# JLPCB_DATA_LOGGER_schematic.net
KiCad netlist of a schematic drawn in EasyEDA
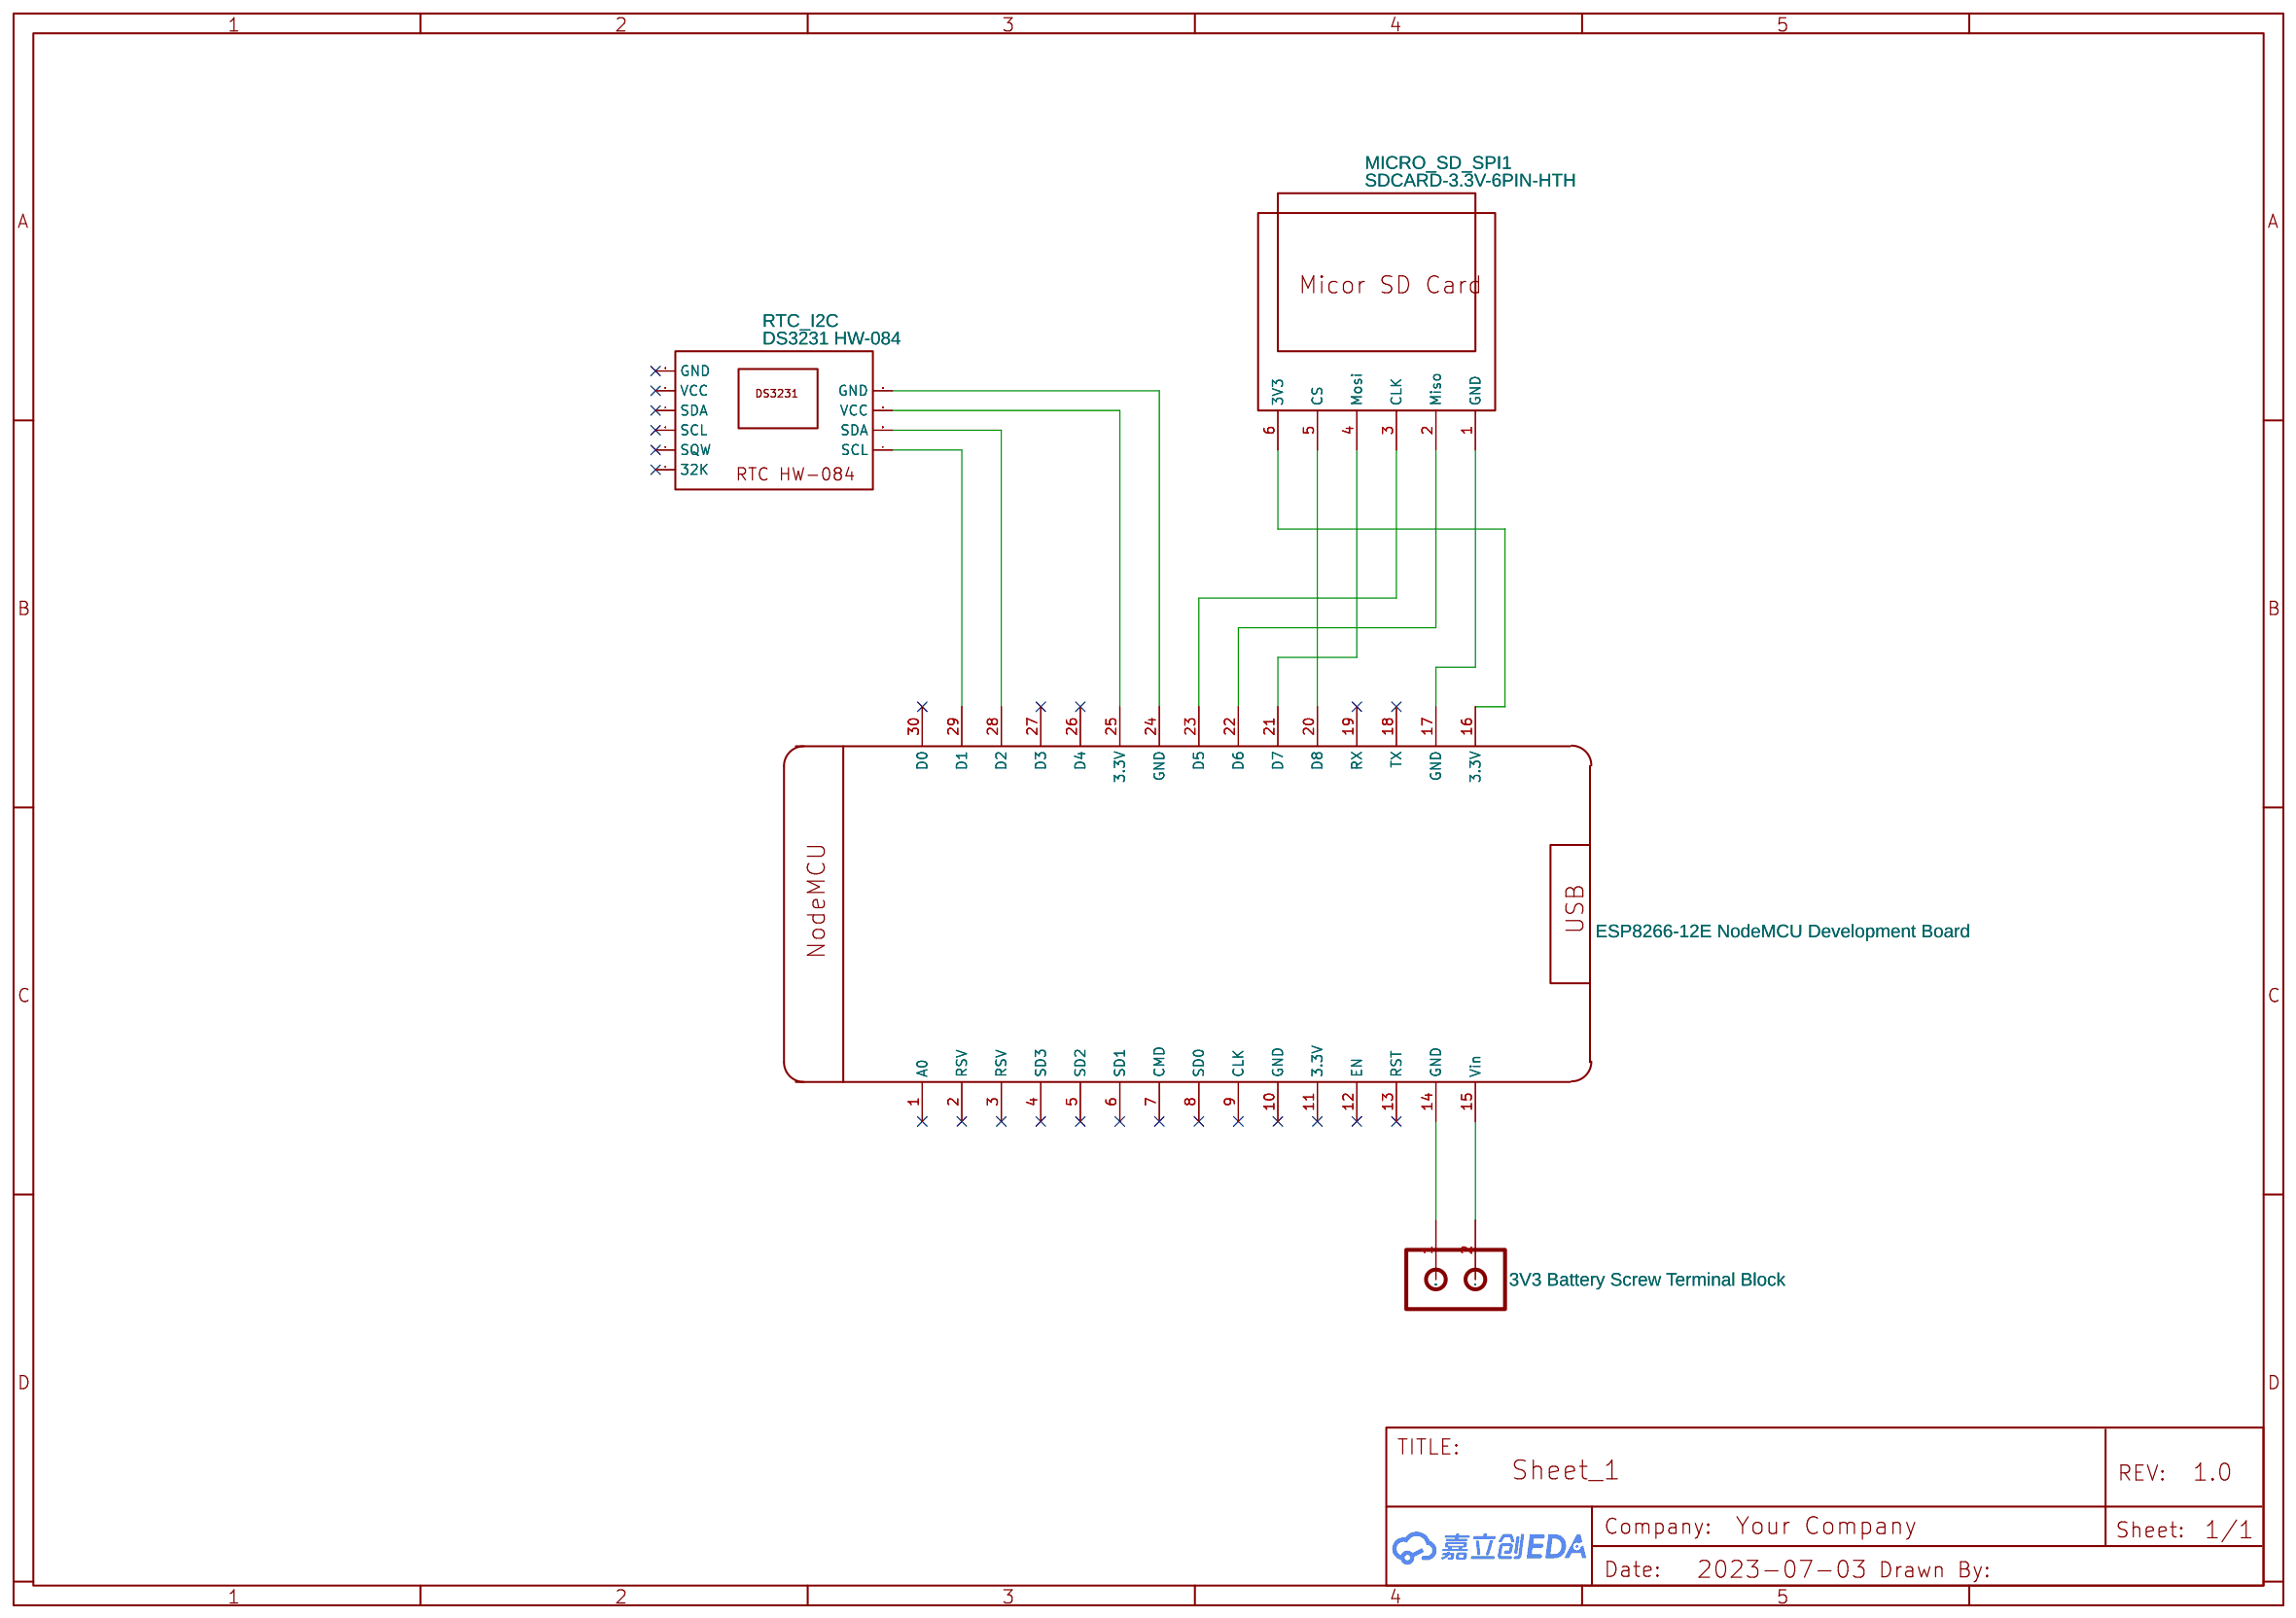
[diagram p0: schematic sheet]

(export (version "E")
  (design (tool "Eeschema 10.0.6"))
  (components
    (comp (ref "MICRO_SD_SPI1")
      (value "SDCARD-3.3V-6PIN-HTH")
      (fields (field (name "BOM_Manufacturer Part") "Aliexpress"))
      (libsource (lib "") (part "SDCARD-3.3V-6PIN-HTH"))
    )
    (comp (ref "NO1")
      (value "3V3 Battery Screw Terminal Block")
      (fields (field (name "BOM_Supplier Part") "HM3173"))
      (libsource (lib "") (part "Screw_Terminal_Block_2_Pin"))
    )
    (comp (ref "RTC_I2C") (value "DS3231 HW-084") (libsource (lib "") (part "DS3231 HW-084")))
    (comp (ref "U1")
      (value "ESP8266-12E NodeMCU Development Board")
      (libsource (lib "") (part "NODEMCU COPY"))
    )
  )
  (nets
    (net (code "1") (name "Net-(MICRO_SD_SPI1-3V3)") (class "Default")
      (node (ref "MICRO_SD_SPI1") (pin "6") (pinfunction "3V3_6") (pintype "unspecified"))
      (node (ref "U1") (pin "16") (pinfunction "3.3V_16") (pintype "unspecified"))
    )
    (net (code "2") (name "Net-(MICRO_SD_SPI1-CLK)") (class "Default")
      (node (ref "MICRO_SD_SPI1") (pin "3") (pinfunction "CLK_3") (pintype "unspecified"))
      (node (ref "U1") (pin "23") (pinfunction "D5_23") (pintype "unspecified"))
    )
    (net (code "3") (name "Net-(MICRO_SD_SPI1-CS)") (class "Default")
      (node (ref "MICRO_SD_SPI1") (pin "5") (pinfunction "CS_5") (pintype "unspecified"))
      (node (ref "U1") (pin "20") (pinfunction "D8_20") (pintype "unspecified"))
    )
    (net (code "4") (name "Net-(MICRO_SD_SPI1-GND)") (class "Default")
      (node (ref "MICRO_SD_SPI1") (pin "1") (pinfunction "GND_1") (pintype "unspecified"))
      (node (ref "U1") (pin "17") (pinfunction "GND_17") (pintype "unspecified"))
    )
    (net (code "5") (name "Net-(MICRO_SD_SPI1-Miso)") (class "Default")
      (node (ref "MICRO_SD_SPI1") (pin "2") (pinfunction "Miso_2") (pintype "unspecified"))
      (node (ref "U1") (pin "22") (pinfunction "D6_22") (pintype "unspecified"))
    )
    (net (code "6") (name "Net-(MICRO_SD_SPI1-Mosi)") (class "Default")
      (node (ref "MICRO_SD_SPI1") (pin "4") (pinfunction "Mosi_4") (pintype "unspecified"))
      (node (ref "U1") (pin "21") (pinfunction "D7_21") (pintype "unspecified"))
    )
    (net (code "7") (name "Net-(NO1-3V3)") (class "Default")
      (node (ref "NO1") (pin "2") (pinfunction "3V3_2") (pintype "passive"))
      (node (ref "U1") (pin "15") (pinfunction "Vin_15") (pintype "unspecified"))
    )
    (net (code "8") (name "Net-(NO1-GND)") (class "Default")
      (node (ref "NO1") (pin "1") (pinfunction "GND_1") (pintype "passive"))
      (node (ref "U1") (pin "14") (pinfunction "GND_14") (pintype "unspecified"))
    )
    (net (code "9") (name "Net-(RTC_I2C-GND-Pad10)") (class "Default")
      (node (ref "RTC_I2C") (pin "10") (pinfunction "GND_10") (pintype "unspecified"))
      (node (ref "U1") (pin "24") (pinfunction "GND_24") (pintype "unspecified"))
    )
    (net (code "10") (name "Net-(RTC_I2C-VCC-Pad9)") (class "Default")
      (node (ref "RTC_I2C") (pin "9") (pinfunction "VCC_9") (pintype "bidirectional"))
      (node (ref "U1") (pin "25") (pinfunction "3.3V_25") (pintype "unspecified"))
    )
    (net (code "11") (name "Net-(U1-D1)") (class "Default")
      (node (ref "RTC_I2C") (pin "7") (pinfunction "SCL_7") (pintype "passive"))
      (node (ref "U1") (pin "29") (pinfunction "D1_29") (pintype "unspecified"))
    )
    (net (code "12") (name "Net-(U1-D2)") (class "Default")
      (node (ref "RTC_I2C") (pin "8") (pinfunction "SDA_8") (pintype "passive"))
      (node (ref "U1") (pin "28") (pinfunction "D2_28") (pintype "unspecified"))
    )
    (net (code "13") (name "unconnected-(RTC_I2C-32K-Pad1)") (class "Default")
      (node (ref "RTC_I2C") (pin "1") (pinfunction "32K_1") (pintype "passive+no_connect"))
    )
    (net (code "14") (name "unconnected-(RTC_I2C-GND-Pad6)") (class "Default")
      (node (ref "RTC_I2C") (pin "6") (pinfunction "GND_6") (pintype "input+no_connect"))
    )
    (net (code "15") (name "unconnected-(RTC_I2C-SCL-Pad3)") (class "Default")
      (node (ref "RTC_I2C") (pin "3") (pinfunction "SCL_3") (pintype "bidirectional+no_connect"))
    )
    (net (code "16") (name "unconnected-(RTC_I2C-SDA-Pad4)") (class "Default")
      (node (ref "RTC_I2C") (pin "4") (pinfunction "SDA_4") (pintype "unspecified+no_connect"))
    )
    (net (code "17") (name "unconnected-(RTC_I2C-SQW-Pad2)") (class "Default")
      (node (ref "RTC_I2C") (pin "2") (pinfunction "SQW_2") (pintype "passive+no_connect"))
    )
    (net (code "18") (name "unconnected-(RTC_I2C-VCC-Pad5)") (class "Default")
      (node (ref "RTC_I2C") (pin "5") (pinfunction "VCC_5") (pintype "input+no_connect"))
    )
    (net (code "19") (name "unconnected-(U1-3.3V-Pad11)") (class "Default")
      (node (ref "U1") (pin "11") (pinfunction "3.3V_11") (pintype "unspecified+no_connect"))
    )
    (net (code "20") (name "unconnected-(U1-A0-Pad1)") (class "Default")
      (node (ref "U1") (pin "1") (pinfunction "A0_1") (pintype "unspecified+no_connect"))
    )
    (net (code "21") (name "unconnected-(U1-CLK-Pad9)") (class "Default")
      (node (ref "U1") (pin "9") (pinfunction "CLK_9") (pintype "unspecified+no_connect"))
    )
    (net (code "22") (name "unconnected-(U1-CMD-Pad7)") (class "Default")
      (node (ref "U1") (pin "7") (pinfunction "CMD_7") (pintype "unspecified+no_connect"))
    )
    (net (code "23") (name "unconnected-(U1-D0-Pad30)") (class "Default")
      (node (ref "U1") (pin "30") (pinfunction "D0_30") (pintype "unspecified+no_connect"))
    )
    (net (code "24") (name "unconnected-(U1-D3-Pad27)") (class "Default")
      (node (ref "U1") (pin "27") (pinfunction "D3_27") (pintype "unspecified+no_connect"))
    )
    (net (code "25") (name "unconnected-(U1-D4-Pad26)") (class "Default")
      (node (ref "U1") (pin "26") (pinfunction "D4_26") (pintype "unspecified+no_connect"))
    )
    (net (code "26") (name "unconnected-(U1-EN-Pad12)") (class "Default")
      (node (ref "U1") (pin "12") (pinfunction "EN_12") (pintype "unspecified+no_connect"))
    )
    (net (code "27") (name "unconnected-(U1-GND-Pad10)") (class "Default")
      (node (ref "U1") (pin "10") (pinfunction "GND_10") (pintype "unspecified+no_connect"))
    )
    (net (code "28") (name "unconnected-(U1-RST-Pad13)") (class "Default")
      (node (ref "U1") (pin "13") (pinfunction "RST_13") (pintype "unspecified+no_connect"))
    )
    (net (code "29") (name "unconnected-(U1-RSV-Pad2)") (class "Default")
      (node (ref "U1") (pin "2") (pinfunction "RSV_2") (pintype "unspecified+no_connect"))
    )
    (net (code "30") (name "unconnected-(U1-RSV-Pad3)") (class "Default")
      (node (ref "U1") (pin "3") (pinfunction "RSV_3") (pintype "unspecified+no_connect"))
    )
    (net (code "31") (name "unconnected-(U1-RX-Pad19)") (class "Default")
      (node (ref "U1") (pin "19") (pinfunction "RX_19") (pintype "unspecified+no_connect"))
    )
    (net (code "32") (name "unconnected-(U1-SD0-Pad8)") (class "Default")
      (node (ref "U1") (pin "8") (pinfunction "SD0_8") (pintype "unspecified+no_connect"))
    )
    (net (code "33") (name "unconnected-(U1-SD1-Pad6)") (class "Default")
      (node (ref "U1") (pin "6") (pinfunction "SD1_6") (pintype "unspecified+no_connect"))
    )
    (net (code "34") (name "unconnected-(U1-SD2-Pad5)") (class "Default")
      (node (ref "U1") (pin "5") (pinfunction "SD2_5") (pintype "unspecified+no_connect"))
    )
    (net (code "35") (name "unconnected-(U1-SD3-Pad4)") (class "Default")
      (node (ref "U1") (pin "4") (pinfunction "SD3_4") (pintype "unspecified+no_connect"))
    )
    (net (code "36") (name "unconnected-(U1-TX-Pad18)") (class "Default")
      (node (ref "U1") (pin "18") (pinfunction "TX_18") (pintype "unspecified+no_connect"))
    )
  )
)
